# Pi_grammer_MAIN.net
KiCad netlist of a schematic drawn in EAGLE
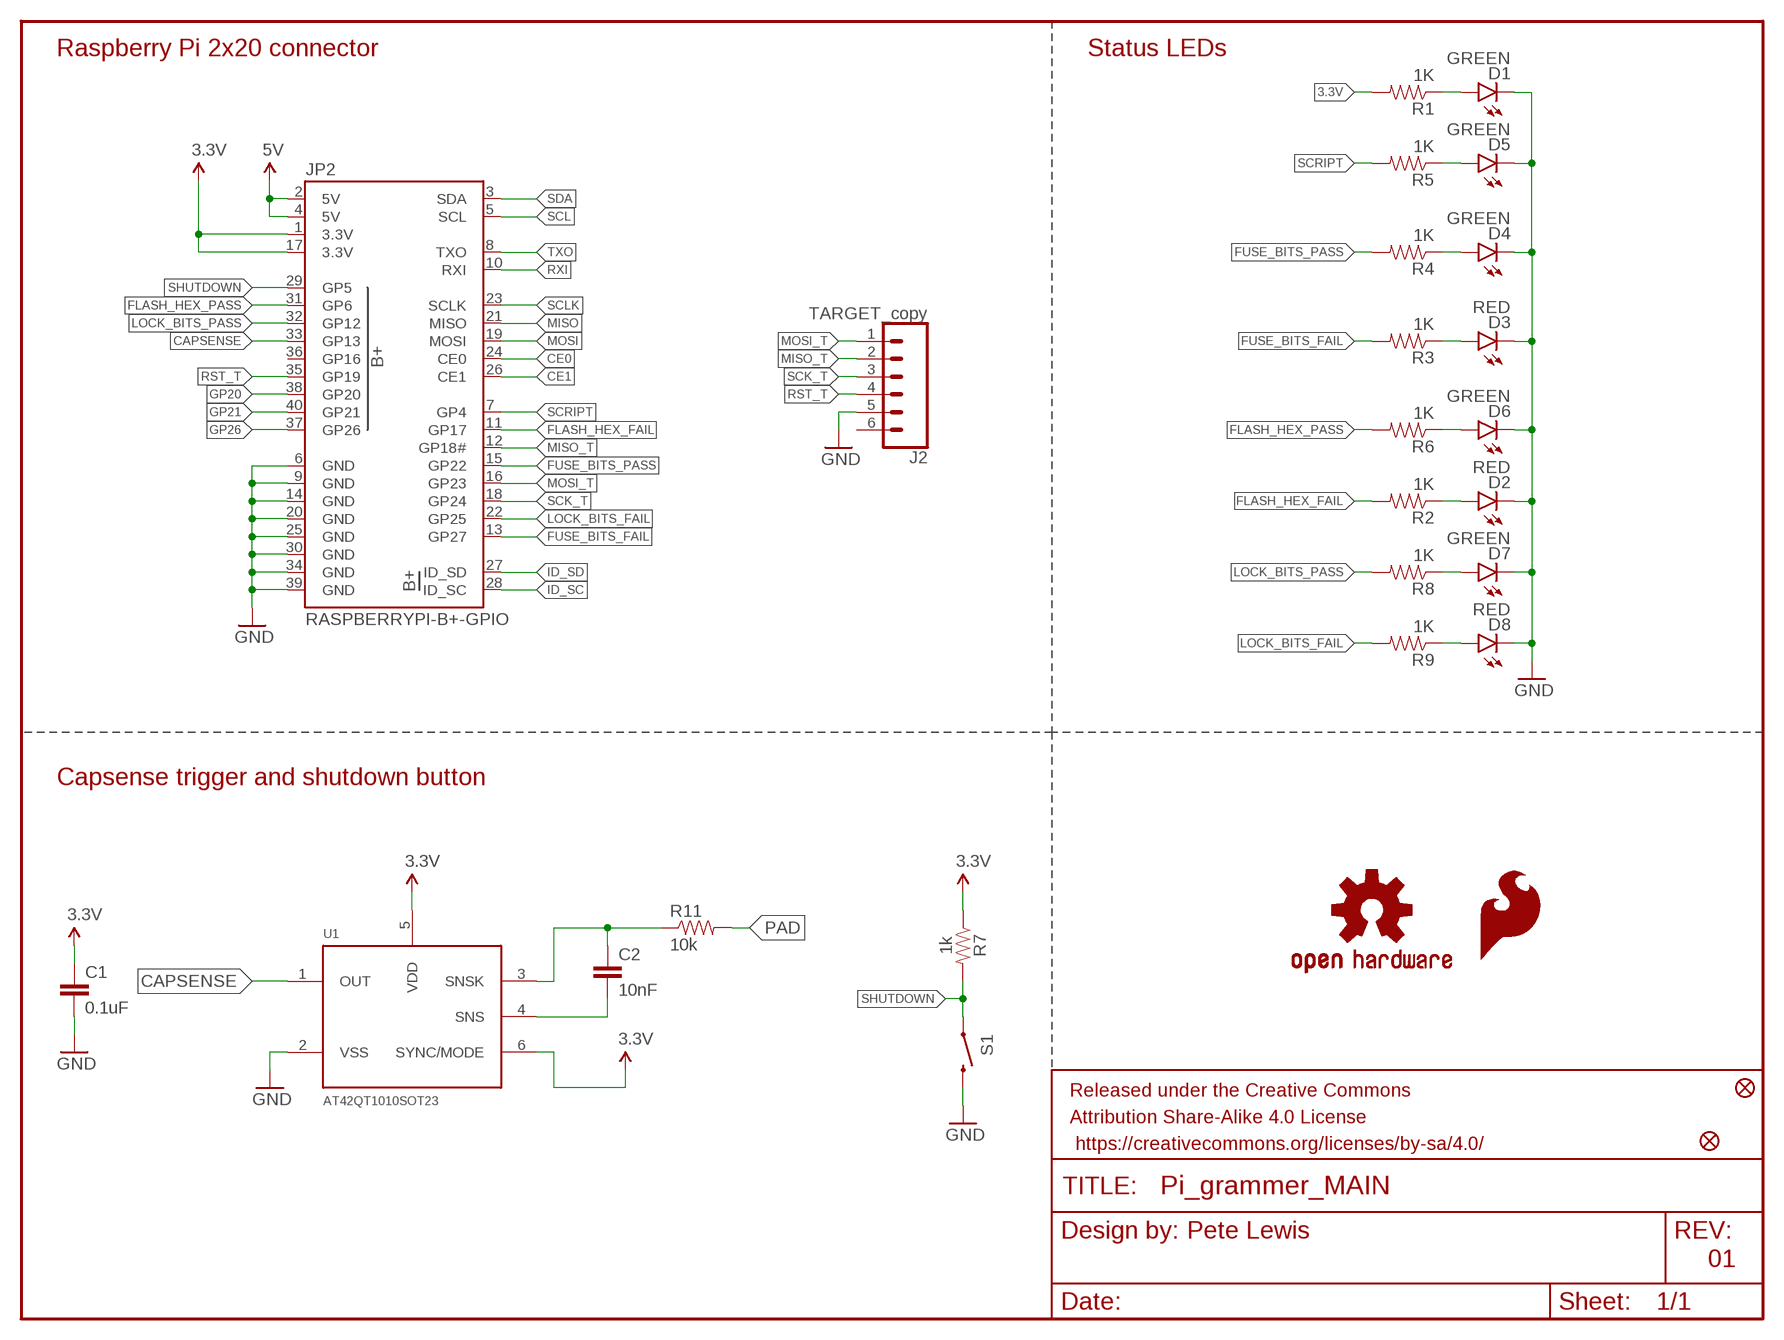
[diagram p0: schematic, sheet 1]

(export (version "E")
  (design (tool "Eeschema 10.0.6"))
  (components
    (comp (ref "C1")
      (value "0.1uF")
      (footprint "eagle-import:0603-CAP")
      (libsource (lib "eagle-import") (part "0.1UF-25V(+80/-20%)(0603)"))
    )
    (comp (ref "C2")
      (value "10nF")
      (footprint "eagle-import:0603-CAP")
      (libsource (lib "eagle-import") (part "10NF/10000PF-50V-10%(0603)"))
    )
    (comp (ref "D1")
      (value "GREEN")
      (footprint "eagle-import:LED-1206")
      (libsource (lib "eagle-import") (part "LED-GREEN1206"))
    )
    (comp (ref "D2")
      (value "RED")
      (footprint "eagle-import:LED-1206")
      (libsource (lib "eagle-import") (part "LED-RED1206"))
    )
    (comp (ref "D3")
      (value "RED")
      (footprint "eagle-import:LED-1206")
      (libsource (lib "eagle-import") (part "LED-RED1206"))
    )
    (comp (ref "D4")
      (value "GREEN")
      (footprint "eagle-import:LED-1206")
      (libsource (lib "eagle-import") (part "LED-GREEN1206"))
    )
    (comp (ref "D5")
      (value "GREEN")
      (footprint "eagle-import:LED-1206")
      (libsource (lib "eagle-import") (part "LED-GREEN1206"))
    )
    (comp (ref "D6")
      (value "GREEN")
      (footprint "eagle-import:LED-1206")
      (libsource (lib "eagle-import") (part "LED-GREEN1206"))
    )
    (comp (ref "D7")
      (value "GREEN")
      (footprint "eagle-import:LED-1206")
      (libsource (lib "eagle-import") (part "LED-GREEN1206"))
    )
    (comp (ref "D8")
      (value "RED")
      (footprint "eagle-import:LED-1206")
      (libsource (lib "eagle-import") (part "LED-RED1206"))
    )
    (comp (ref "FD1")
      (value "FIDUCIALUFIDUCIAL")
      (footprint "eagle-import:FIDUCIAL-MICRO")
      (libsource (lib "eagle-import") (part "FIDUCIALUFIDUCIAL"))
    )
    (comp (ref "FD2")
      (value "FIDUCIALUFIDUCIAL")
      (footprint "eagle-import:FIDUCIAL-MICRO")
      (libsource (lib "eagle-import") (part "FIDUCIALUFIDUCIAL"))
    )
    (comp (ref "FRAME1")
      (value "FRAME-LETTER")
      (footprint "eagle-import:CREATIVE_COMMONS")
      (libsource (lib "eagle-import") (part "FRAME-LETTER"))
    )
    (comp (ref "J2")
      (value "TARGET_copy")
      (footprint "eagle-import:MOLEX-1X6")
      (libsource (lib "eagle-import") (part "CONN_06POLAR"))
    )
    (comp (ref "JP2")
      (value "RASPBERRYPI-B+-GPIO")
      (footprint "eagle-import:2X20-SHROUDED")
      (libsource (lib "eagle-import") (part "RASPBERRYPI-B+-GPIO"))
    )
    (comp (ref "LOGO1")
      (value "SFE_LOGO_FLAME.1_INCH")
      (footprint "eagle-import:SFE_LOGO_FLAME_.1")
      (libsource (lib "eagle-import") (part "SFE_LOGO_FLAME.1_INCH"))
    )
    (comp (ref "LOGO2")
      (value "OSHW-LOGOS")
      (footprint "eagle-import:OSHW-LOGO-S")
      (libsource (lib "eagle-import") (part "OSHW-LOGOS"))
    )
    (comp (ref "R1")
      (value "1K")
      (footprint "eagle-import:0603-RES")
      (libsource (lib "eagle-import") (part "1KOHM-1/10W-1%(0603)"))
    )
    (comp (ref "R2")
      (value "1K")
      (footprint "eagle-import:0603-RES")
      (libsource (lib "eagle-import") (part "1KOHM-1/10W-1%(0603)"))
    )
    (comp (ref "R3")
      (value "1K")
      (footprint "eagle-import:0603-RES")
      (libsource (lib "eagle-import") (part "1KOHM-1/10W-1%(0603)"))
    )
    (comp (ref "R4")
      (value "1K")
      (footprint "eagle-import:0603-RES")
      (libsource (lib "eagle-import") (part "1KOHM-1/10W-1%(0603)"))
    )
    (comp (ref "R5")
      (value "1K")
      (footprint "eagle-import:0603-RES")
      (libsource (lib "eagle-import") (part "1KOHM-1/10W-1%(0603)"))
    )
    (comp (ref "R6")
      (value "1K")
      (footprint "eagle-import:0603-RES")
      (libsource (lib "eagle-import") (part "1KOHM-1/10W-1%(0603)"))
    )
    (comp (ref "R7")
      (value "1k")
      (footprint "eagle-import:0603")
      (libsource (lib "eagle-import") (part "1KOHM-0603-1/10W-1%"))
    )
    (comp (ref "R8")
      (value "1K")
      (footprint "eagle-import:0603-RES")
      (libsource (lib "eagle-import") (part "1KOHM-1/10W-1%(0603)"))
    )
    (comp (ref "R9")
      (value "1K")
      (footprint "eagle-import:0603-RES")
      (libsource (lib "eagle-import") (part "1KOHM-1/10W-1%(0603)"))
    )
    (comp (ref "R11")
      (value "10k")
      (footprint "eagle-import:0603-RES")
      (libsource (lib "eagle-import") (part "10KOHM-1/10W-1%(0603)0603"))
    )
    (comp (ref "S1")
      (value "SWITCH-MOMENTARY-2SMD")
      (footprint "eagle-import:TACTILE-SWITCH-SMD")
      (libsource (lib "eagle-import") (part "SWITCH-MOMENTARY-2SMD"))
    )
    (comp (ref "U1")
      (value "AT42QT1010SOT23")
      (footprint "eagle-import:SOT23-6")
      (libsource (lib "eagle-import") (part "AT42QT1010SOT23"))
    )
  )
  (nets
    (net (code "1") (name "3.3V") (class "Default")
      (node (ref "C1") (pin "1") (pinfunction "1_1") (pintype "passive"))
      (node (ref "JP2") (pin "1") (pinfunction "3.3V_1") (pintype "power_in"))
      (node (ref "JP2") (pin "17") (pinfunction "3.3V_17") (pintype "power_in"))
      (node (ref "R1") (pin "2") (pinfunction "2_2") (pintype "passive"))
      (node (ref "R7") (pin "1") (pinfunction "1_1") (pintype "passive"))
      (node (ref "U1") (pin "5") (pinfunction "VDD_5") (pintype "bidirectional"))
      (node (ref "U1") (pin "6") (pinfunction "SYNC/MODE_6") (pintype "bidirectional"))
    )
    (net (code "2") (name "5V") (class "Default")
      (node (ref "JP2") (pin "2") (pinfunction "5V_2") (pintype "power_in"))
      (node (ref "JP2") (pin "4") (pinfunction "5V_4") (pintype "power_in"))
    )
    (net (code "3") (name "CAPSENSE") (class "Default")
      (node (ref "JP2") (pin "33") (pinfunction "GP13_33") (pintype "bidirectional"))
      (node (ref "U1") (pin "1") (pinfunction "OUT_1") (pintype "bidirectional"))
    )
    (net (code "4") (name "CE0") (class "Default")
      (node (ref "JP2") (pin "24") (pinfunction "CE0_24") (pintype "output"))
    )
    (net (code "5") (name "CE1") (class "Default")
      (node (ref "JP2") (pin "26") (pinfunction "CE1_26") (pintype "output"))
    )
    (net (code "6") (name "FLASH_HEX_FAIL") (class "Default")
      (node (ref "JP2") (pin "11") (pinfunction "GP17_11") (pintype "bidirectional"))
      (node (ref "R2") (pin "2") (pinfunction "2_2") (pintype "passive"))
    )
    (net (code "7") (name "FLASH_HEX_PASS") (class "Default")
      (node (ref "JP2") (pin "31") (pinfunction "GP6_31") (pintype "bidirectional"))
      (node (ref "R6") (pin "2") (pinfunction "2_2") (pintype "passive"))
    )
    (net (code "8") (name "FUSE_BITS_FAIL") (class "Default")
      (node (ref "JP2") (pin "13") (pinfunction "GP27_13") (pintype "bidirectional"))
      (node (ref "R3") (pin "2") (pinfunction "2_2") (pintype "passive"))
    )
    (net (code "9") (name "FUSE_BITS_PASS") (class "Default")
      (node (ref "JP2") (pin "15") (pinfunction "GP22_15") (pintype "bidirectional"))
      (node (ref "R4") (pin "2") (pinfunction "2_2") (pintype "passive"))
    )
    (net (code "10") (name "GND") (class "Default")
      (node (ref "C1") (pin "2") (pinfunction "2_2") (pintype "passive"))
      (node (ref "D1") (pin "C") (pinfunction "C_C") (pintype "passive"))
      (node (ref "D2") (pin "C") (pinfunction "C_C") (pintype "passive"))
      (node (ref "D3") (pin "C") (pinfunction "C_C") (pintype "passive"))
      (node (ref "D4") (pin "C") (pinfunction "C_C") (pintype "passive"))
      (node (ref "D5") (pin "C") (pinfunction "C_C") (pintype "passive"))
      (node (ref "D6") (pin "C") (pinfunction "C_C") (pintype "passive"))
      (node (ref "D7") (pin "C") (pinfunction "C_C") (pintype "passive"))
      (node (ref "D8") (pin "C") (pinfunction "C_C") (pintype "passive"))
      (node (ref "J2") (pin "5") (pinfunction "5_5") (pintype "passive"))
      (node (ref "JP2") (pin "14") (pinfunction "GND_14") (pintype "power_in"))
      (node (ref "JP2") (pin "20") (pinfunction "GND_20") (pintype "power_in"))
      (node (ref "JP2") (pin "25") (pinfunction "GND_25") (pintype "power_in"))
      (node (ref "JP2") (pin "30") (pinfunction "GND_30") (pintype "power_in"))
      (node (ref "JP2") (pin "34") (pinfunction "GND_34") (pintype "power_in"))
      (node (ref "JP2") (pin "39") (pinfunction "GND_39") (pintype "power_in"))
      (node (ref "JP2") (pin "6") (pinfunction "GND_6") (pintype "power_in"))
      (node (ref "JP2") (pin "9") (pinfunction "GND_9") (pintype "power_in"))
      (node (ref "S1") (pin "3") (pinfunction "2_3") (pintype "passive"))
      (node (ref "U1") (pin "2") (pinfunction "VSS_2") (pintype "bidirectional"))
    )
    (net (code "11") (name "GP20") (class "Default")
      (node (ref "JP2") (pin "38") (pinfunction "GP20_38") (pintype "bidirectional"))
    )
    (net (code "12") (name "GP21") (class "Default")
      (node (ref "JP2") (pin "40") (pinfunction "GP21_40") (pintype "bidirectional"))
    )
    (net (code "13") (name "GP26") (class "Default")
      (node (ref "JP2") (pin "37") (pinfunction "GP26_37") (pintype "bidirectional"))
    )
    (net (code "14") (name "ID_SC") (class "Default")
      (node (ref "JP2") (pin "28") (pinfunction "ID_SC_28") (pintype "bidirectional"))
    )
    (net (code "15") (name "ID_SD") (class "Default")
      (node (ref "JP2") (pin "27") (pinfunction "ID_SD_27") (pintype "bidirectional"))
    )
    (net (code "16") (name "LOCK_BITS_FAIL") (class "Default")
      (node (ref "JP2") (pin "22") (pinfunction "GP25_22") (pintype "bidirectional"))
      (node (ref "R9") (pin "2") (pinfunction "2_2") (pintype "passive"))
    )
    (net (code "17") (name "LOCK_BITS_PASS") (class "Default")
      (node (ref "JP2") (pin "32") (pinfunction "GP12_32") (pintype "bidirectional"))
      (node (ref "R8") (pin "2") (pinfunction "2_2") (pintype "passive"))
    )
    (net (code "18") (name "MISO") (class "Default")
      (node (ref "JP2") (pin "21") (pinfunction "MISO_21") (pintype "input"))
    )
    (net (code "19") (name "MISO_T") (class "Default")
      (node (ref "J2") (pin "2") (pinfunction "2_2") (pintype "passive"))
      (node (ref "JP2") (pin "12") (pinfunction "GP18#_12") (pintype "bidirectional"))
    )
    (net (code "20") (name "MOSI") (class "Default")
      (node (ref "JP2") (pin "19") (pinfunction "MOSI_19") (pintype "output"))
    )
    (net (code "21") (name "MOSI_T") (class "Default")
      (node (ref "J2") (pin "1") (pinfunction "1_1") (pintype "passive"))
      (node (ref "JP2") (pin "16") (pinfunction "GP23_16") (pintype "bidirectional"))
    )
    (net (code "22") (name "Net-(D1-PadA)") (class "Default")
      (node (ref "D1") (pin "A") (pinfunction "A_A") (pintype "passive"))
      (node (ref "R1") (pin "1") (pinfunction "1_1") (pintype "passive"))
    )
    (net (code "23") (name "Net-(D2-PadA)") (class "Default")
      (node (ref "D2") (pin "A") (pinfunction "A_A") (pintype "passive"))
      (node (ref "R2") (pin "1") (pinfunction "1_1") (pintype "passive"))
    )
    (net (code "24") (name "Net-(D3-PadA)") (class "Default")
      (node (ref "D3") (pin "A") (pinfunction "A_A") (pintype "passive"))
      (node (ref "R3") (pin "1") (pinfunction "1_1") (pintype "passive"))
    )
    (net (code "25") (name "Net-(D4-PadA)") (class "Default")
      (node (ref "D4") (pin "A") (pinfunction "A_A") (pintype "passive"))
      (node (ref "R4") (pin "1") (pinfunction "1_1") (pintype "passive"))
    )
    (net (code "26") (name "Net-(D5-PadA)") (class "Default")
      (node (ref "D5") (pin "A") (pinfunction "A_A") (pintype "passive"))
      (node (ref "R5") (pin "1") (pinfunction "1_1") (pintype "passive"))
    )
    (net (code "27") (name "Net-(D6-PadA)") (class "Default")
      (node (ref "D6") (pin "A") (pinfunction "A_A") (pintype "passive"))
      (node (ref "R6") (pin "1") (pinfunction "1_1") (pintype "passive"))
    )
    (net (code "28") (name "Net-(D7-PadA)") (class "Default")
      (node (ref "D7") (pin "A") (pinfunction "A_A") (pintype "passive"))
      (node (ref "R8") (pin "1") (pinfunction "1_1") (pintype "passive"))
    )
    (net (code "29") (name "Net-(D8-PadA)") (class "Default")
      (node (ref "D8") (pin "A") (pinfunction "A_A") (pintype "passive"))
      (node (ref "R9") (pin "1") (pinfunction "1_1") (pintype "passive"))
    )
    (net (code "30") (name "Net-(U1-SNS)") (class "Default")
      (node (ref "C2") (pin "2") (pinfunction "2_2") (pintype "passive"))
      (node (ref "U1") (pin "4") (pinfunction "SNS_4") (pintype "bidirectional"))
    )
    (net (code "31") (name "Net-(U1-SNSK)") (class "Default")
      (node (ref "C2") (pin "1") (pinfunction "1_1") (pintype "passive"))
      (node (ref "R11") (pin "1") (pinfunction "1_1") (pintype "passive"))
      (node (ref "U1") (pin "3") (pinfunction "SNSK_3") (pintype "bidirectional"))
    )
    (net (code "32") (name "PAD") (class "Default")
      (node (ref "R11") (pin "2") (pinfunction "2_2") (pintype "passive"))
    )
    (net (code "33") (name "RST_T") (class "Default")
      (node (ref "J2") (pin "4") (pinfunction "4_4") (pintype "passive"))
      (node (ref "JP2") (pin "35") (pinfunction "GP19_35") (pintype "bidirectional"))
    )
    (net (code "34") (name "RXI") (class "Default")
      (node (ref "JP2") (pin "10") (pinfunction "RXI_10") (pintype "input"))
    )
    (net (code "35") (name "SCK_T") (class "Default")
      (node (ref "J2") (pin "3") (pinfunction "3_3") (pintype "passive"))
      (node (ref "JP2") (pin "18") (pinfunction "GP24_18") (pintype "bidirectional"))
    )
    (net (code "36") (name "SCL") (class "Default")
      (node (ref "JP2") (pin "5") (pinfunction "SCL_5") (pintype "bidirectional"))
    )
    (net (code "37") (name "SCLK") (class "Default")
      (node (ref "JP2") (pin "23") (pinfunction "SCLK_23") (pintype "output"))
    )
    (net (code "38") (name "SCRIPT") (class "Default")
      (node (ref "JP2") (pin "7") (pinfunction "GP4_7") (pintype "bidirectional"))
      (node (ref "R5") (pin "2") (pinfunction "2_2") (pintype "passive"))
    )
    (net (code "39") (name "SDA") (class "Default")
      (node (ref "JP2") (pin "3") (pinfunction "SDA_3") (pintype "bidirectional"))
    )
    (net (code "40") (name "SHUTDOWN") (class "Default")
      (node (ref "JP2") (pin "29") (pinfunction "GP5_29") (pintype "bidirectional"))
      (node (ref "R7") (pin "2") (pinfunction "2_2") (pintype "passive"))
      (node (ref "S1") (pin "1") (pinfunction "1_1") (pintype "passive"))
    )
    (net (code "41") (name "TXO") (class "Default")
      (node (ref "JP2") (pin "8") (pinfunction "TXO_8") (pintype "output"))
    )
    (net (code "42") (name "unconnected-(J2-Pad6)") (class "Default")
      (node (ref "J2") (pin "6") (pinfunction "6_6") (pintype "passive"))
    )
    (net (code "43") (name "unconnected-(JP2-GP16-Pad36)") (class "Default")
      (node (ref "JP2") (pin "36") (pinfunction "GP16_36") (pintype "bidirectional"))
    )
  )
)
